# pico_test.net
KiCad netlist of a schematic drawn in EAGLE
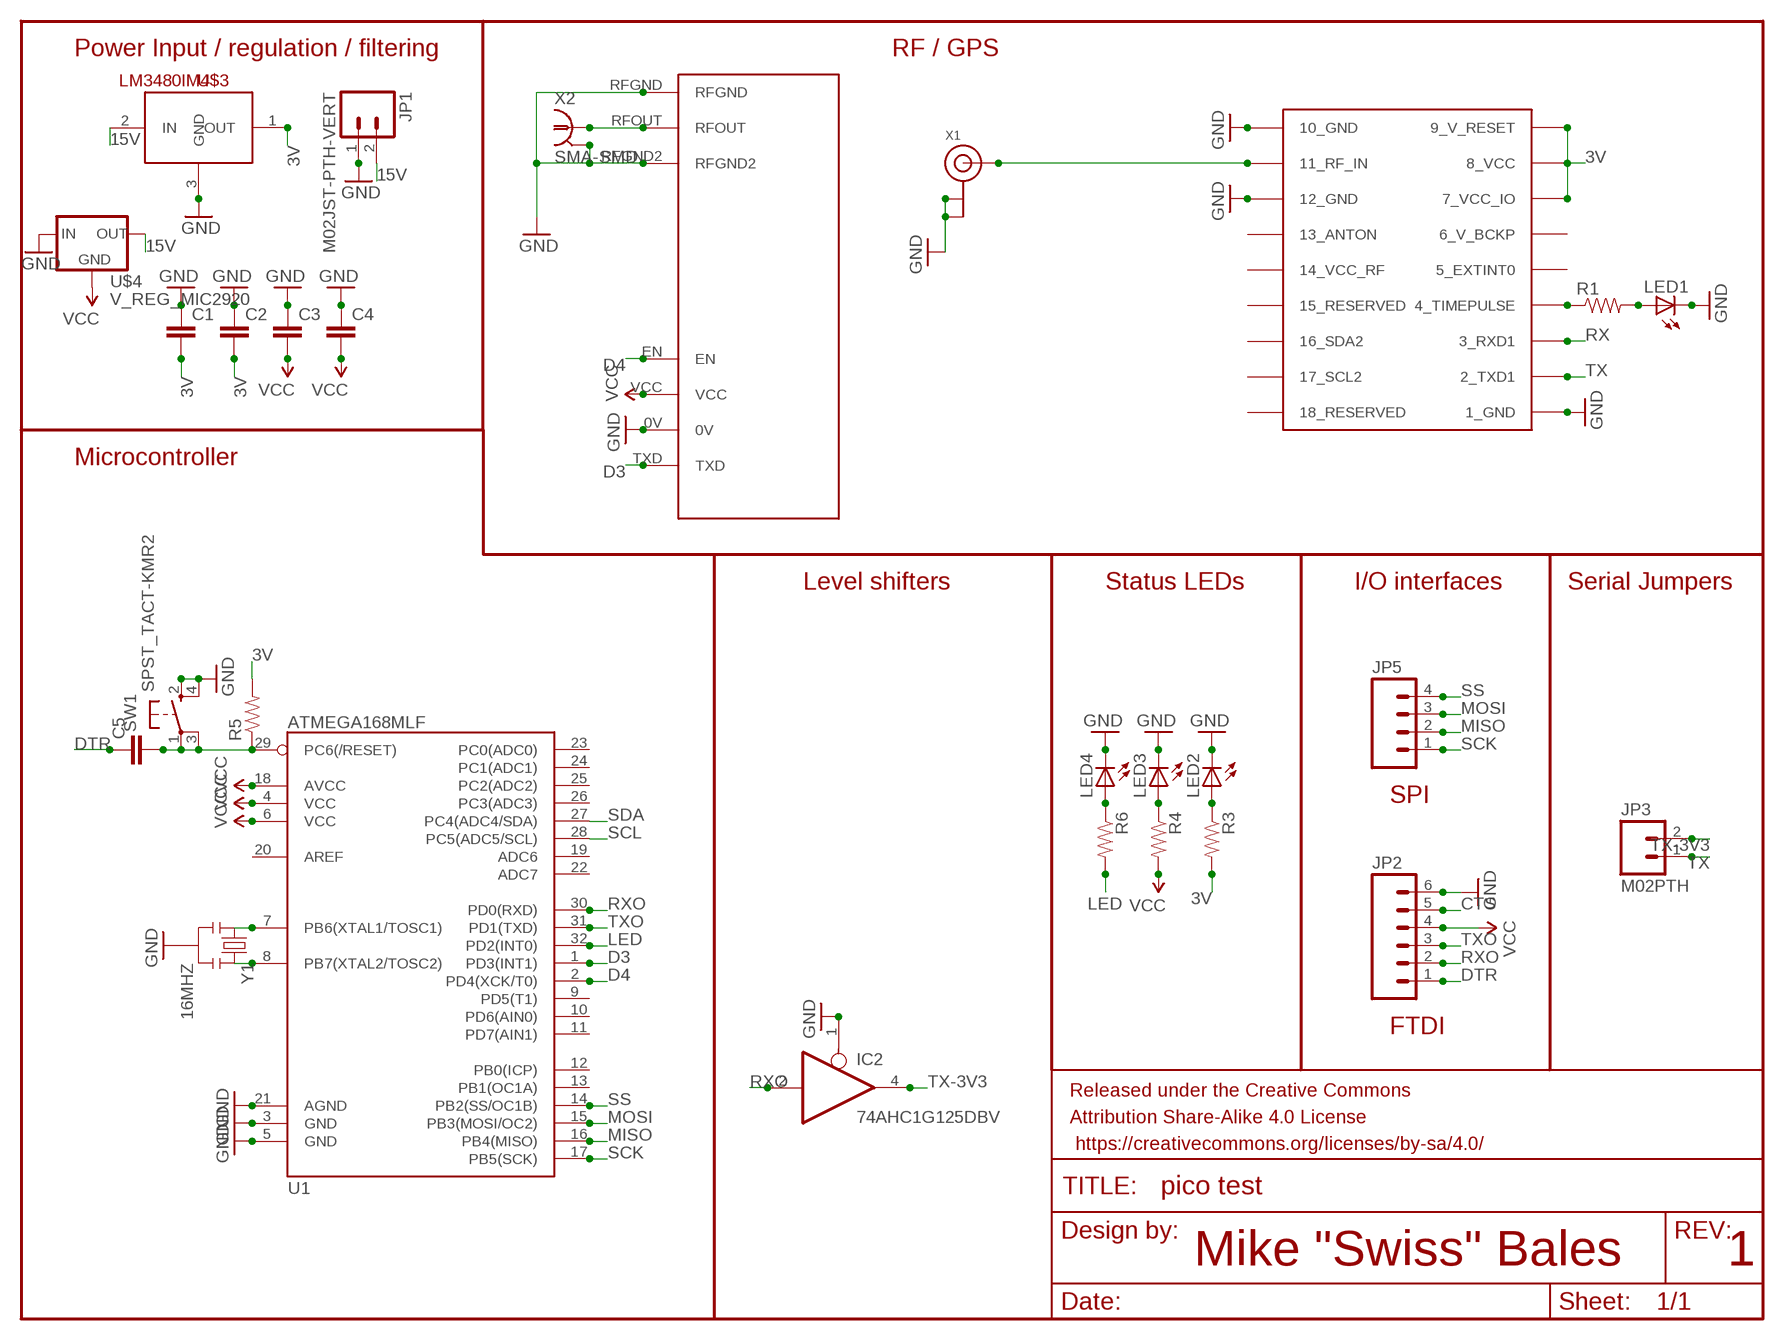
[diagram p0: schematic, sheet 1]

(export (version "E")
  (design (tool "Eeschema 10.0.6"))
  (components
    (comp (ref "C1")
      (value "CAP0805")
      (footprint "eagle-import:0805")
      (libsource (lib "eagle-import") (part "CAP0805"))
    )
    (comp (ref "C2")
      (value "CAP0805")
      (footprint "eagle-import:0805")
      (libsource (lib "eagle-import") (part "CAP0805"))
    )
    (comp (ref "C3")
      (value "CAP0805")
      (footprint "eagle-import:0805")
      (libsource (lib "eagle-import") (part "CAP0805"))
    )
    (comp (ref "C4")
      (value "CAP0805")
      (footprint "eagle-import:0805")
      (libsource (lib "eagle-import") (part "CAP0805"))
    )
    (comp (ref "C5")
      (value "CAP0805")
      (footprint "eagle-import:0805")
      (libsource (lib "eagle-import") (part "CAP0805"))
    )
    (comp (ref "FRAME1")
      (value "FRAME-LETTER")
      (footprint "eagle-import:CREATIVE_COMMONS")
      (libsource (lib "eagle-import") (part "FRAME-LETTER"))
    )
    (comp (ref "IC2")
      (value "74AHC1G125DBV")
      (footprint "eagle-import:SOT23-5")
      (libsource (lib "eagle-import") (part "741G125DBVAHC"))
    )
    (comp (ref "JP1")
      (value "M02JST-PTH-VERT")
      (footprint "eagle-import:JST-2-PTH-VERT")
      (libsource (lib "eagle-import") (part "M02JST-PTH-VERT"))
    )
    (comp (ref "JP2")
      (value "M06NO_SILK_FEMALE_PTH")
      (footprint "eagle-import:1X06_NO_SILK")
      (libsource (lib "eagle-import") (part "M06NO_SILK_FEMALE_PTH"))
    )
    (comp (ref "JP3")
      (value "M02PTH")
      (footprint "eagle-import:1X02")
      (libsource (lib "eagle-import") (part "M02PTH"))
    )
    (comp (ref "JP5")
      (value "M041X04_NO_SILK")
      (footprint "eagle-import:1X04_NO_SILK")
      (libsource (lib "eagle-import") (part "M041X04_NO_SILK"))
    )
    (comp (ref "LED1")
      (value "LEDCHIP-LED0805")
      (footprint "eagle-import:CHIP-LED0805")
      (libsource (lib "eagle-import") (part "LEDCHIP-LED0805"))
    )
    (comp (ref "LED2")
      (value "LEDCHIP-LED0805")
      (footprint "eagle-import:CHIP-LED0805")
      (libsource (lib "eagle-import") (part "LEDCHIP-LED0805"))
    )
    (comp (ref "LED3")
      (value "LEDCHIP-LED0805")
      (footprint "eagle-import:CHIP-LED0805")
      (libsource (lib "eagle-import") (part "LEDCHIP-LED0805"))
    )
    (comp (ref "LED4")
      (value "LEDCHIP-LED0805")
      (footprint "eagle-import:CHIP-LED0805")
      (libsource (lib "eagle-import") (part "LEDCHIP-LED0805"))
    )
    (comp (ref "R1")
      (value "RESISTOR0805-RES")
      (footprint "eagle-import:0805")
      (libsource (lib "eagle-import") (part "RESISTOR0805-RES"))
    )
    (comp (ref "R3")
      (value "RESISTOR0805-RES")
      (footprint "eagle-import:0805")
      (libsource (lib "eagle-import") (part "RESISTOR0805-RES"))
    )
    (comp (ref "R4")
      (value "RESISTOR0805-RES")
      (footprint "eagle-import:0805")
      (libsource (lib "eagle-import") (part "RESISTOR0805-RES"))
    )
    (comp (ref "R5")
      (value "RESISTOR0805-RES")
      (footprint "eagle-import:0805")
      (libsource (lib "eagle-import") (part "RESISTOR0805-RES"))
    )
    (comp (ref "R6")
      (value "RESISTOR0805-RES")
      (footprint "eagle-import:0805")
      (libsource (lib "eagle-import") (part "RESISTOR0805-RES"))
    )
    (comp (ref "SW1")
      (value "SPST_TACT-KMR2")
      (footprint "eagle-import:KMR2")
      (libsource (lib "eagle-import") (part "SPST_TACT-KMR2"))
    )
    (comp (ref "U$1")
      (value "UBLOX_MAX")
      (footprint "eagle-import:UBLOX_MAX")
      (libsource (lib "eagle-import") (part "UBLOX_MAX"))
    )
    (comp (ref "U$2")
      (value "RADIOMETRIX-HX1")
      (footprint "eagle-import:RADIOMETRIX-HX1")
      (libsource (lib "eagle-import") (part "RADIOMETRIX-HX1"))
    )
    (comp (ref "U$3")
      (value "LM3480IM4")
      (footprint "eagle-import:SOT23-3")
      (libsource (lib "eagle-import") (part "LM3480IM4"))
    )
    (comp (ref "U$4")
      (value "V_REG_MIC2920")
      (footprint "eagle-import:SOT223")
      (libsource (lib "eagle-import") (part "V_REG_MIC2920"))
    )
    (comp (ref "U1")
      (value "ATMEGA168MLF")
      (footprint "eagle-import:MLF32")
      (libsource (lib "eagle-import") (part "ATMEGA168MLF"))
    )
    (comp (ref "X1")
      (value "ANTENNA_U.FL")
      (footprint "eagle-import:U.FL")
      (libsource (lib "eagle-import") (part "ANTENNA_U.FL"))
    )
    (comp (ref "X2")
      (value "SMA-SMD")
      (footprint "eagle-import:SMA-SMD")
      (libsource (lib "eagle-import") (part "SMA-SMD"))
    )
    (comp (ref "Y1")
      (value "16MHZ")
      (footprint "eagle-import:RESONATOR-SMD")
      (libsource (lib "eagle-import") (part "RESONATOR16MHZ"))
    )
  )
  (nets
    (net (code "1") (name "/3V") (class "Default")
      (node (ref "C1") (pin "2") (pinfunction "2_2") (pintype "passive"))
      (node (ref "C2") (pin "2") (pinfunction "2_2") (pintype "passive"))
      (node (ref "R3") (pin "2") (pinfunction "2_2") (pintype "passive"))
      (node (ref "R5") (pin "2") (pinfunction "2_2") (pintype "passive"))
      (node (ref "U$1") (pin "7_VCC_IO") (pinfunction "7_VCC_IO_7_VCC_IO") (pintype "power_in"))
      (node (ref "U$1") (pin "8_VCC") (pinfunction "8_VCC_8_VCC") (pintype "power_in"))
      (node (ref "U$1") (pin "9_V_RESET") (pinfunction "9_V_RESET_9_V_RESET") (pintype "power_in"))
      (node (ref "U$3") (pin "1") (pinfunction "OUT_1") (pintype "bidirectional"))
    )
    (net (code "2") (name "/15V") (class "Default")
      (node (ref "JP1") (pin "2") (pinfunction "2_2") (pintype "passive"))
      (node (ref "U$3") (pin "2") (pinfunction "IN_2") (pintype "bidirectional"))
      (node (ref "U$4") (pin "3") (pinfunction "OUT_3") (pintype "output"))
    )
    (net (code "3") (name "/CTS") (class "Default")
      (node (ref "JP2") (pin "5") (pinfunction "5_5") (pintype "passive"))
    )
    (net (code "4") (name "/D3") (class "Default")
      (node (ref "U$2") (pin "TXD") (pinfunction "TXD_TXD") (pintype "bidirectional"))
      (node (ref "U1") (pin "1") (pinfunction "PD3(INT1)_1") (pintype "bidirectional"))
    )
    (net (code "5") (name "/D4") (class "Default")
      (node (ref "U$2") (pin "EN") (pinfunction "EN_EN") (pintype "bidirectional"))
      (node (ref "U1") (pin "2") (pinfunction "PD4(XCK/T0)_2") (pintype "bidirectional"))
    )
    (net (code "6") (name "/DTR") (class "Default")
      (node (ref "C5") (pin "1") (pinfunction "1_1") (pintype "passive"))
      (node (ref "JP2") (pin "1") (pinfunction "1_1") (pintype "passive"))
    )
    (net (code "7") (name "/LED") (class "Default")
      (node (ref "R6") (pin "2") (pinfunction "2_2") (pintype "passive"))
      (node (ref "U1") (pin "32") (pinfunction "PD2(INT0)_32") (pintype "bidirectional"))
    )
    (net (code "8") (name "/MISO") (class "Default")
      (node (ref "JP5") (pin "2") (pinfunction "2_2") (pintype "passive"))
      (node (ref "U1") (pin "16") (pinfunction "PB4(MISO)_16") (pintype "bidirectional"))
    )
    (net (code "9") (name "/MOSI") (class "Default")
      (node (ref "JP5") (pin "3") (pinfunction "3_3") (pintype "passive"))
      (node (ref "U1") (pin "15") (pinfunction "PB3(MOSI/OC2)_15") (pintype "bidirectional"))
    )
    (net (code "10") (name "/RX") (class "Default")
      (node (ref "U$1") (pin "3_RXD1") (pinfunction "3_RXD1_3_RXD1") (pintype "bidirectional"))
    )
    (net (code "11") (name "/RXO") (class "Default")
      (node (ref "IC2") (pin "2") (pinfunction "I_2") (pintype "input"))
      (node (ref "JP2") (pin "2") (pinfunction "2_2") (pintype "passive"))
      (node (ref "U1") (pin "30") (pinfunction "PD0(RXD)_30") (pintype "bidirectional"))
    )
    (net (code "12") (name "/SCK") (class "Default")
      (node (ref "JP5") (pin "1") (pinfunction "1_1") (pintype "passive"))
      (node (ref "U1") (pin "17") (pinfunction "PB5(SCK)_17") (pintype "bidirectional"))
    )
    (net (code "13") (name "/SCL") (class "Default")
      (node (ref "U1") (pin "28") (pinfunction "PC5(ADC5/SCL)_28") (pintype "bidirectional"))
    )
    (net (code "14") (name "/SDA") (class "Default")
      (node (ref "U1") (pin "27") (pinfunction "PC4(ADC4/SDA)_27") (pintype "bidirectional"))
    )
    (net (code "15") (name "/SS") (class "Default")
      (node (ref "JP5") (pin "4") (pinfunction "4_4") (pintype "passive"))
      (node (ref "U1") (pin "14") (pinfunction "PB2(SS/OC1B)_14") (pintype "bidirectional"))
    )
    (net (code "16") (name "/TX") (class "Default")
      (node (ref "JP3") (pin "1") (pinfunction "1_1") (pintype "passive"))
      (node (ref "U$1") (pin "2_TXD1") (pinfunction "2_TXD1_2_TXD1") (pintype "bidirectional"))
    )
    (net (code "17") (name "/TX-3V3") (class "Default")
      (node (ref "IC2") (pin "4") (pinfunction "O_4") (pintype "tri_state"))
      (node (ref "JP3") (pin "2") (pinfunction "2_2") (pintype "passive"))
    )
    (net (code "18") (name "/TXO") (class "Default")
      (node (ref "JP2") (pin "3") (pinfunction "3_3") (pintype "passive"))
      (node (ref "U1") (pin "31") (pinfunction "PD1(TXD)_31") (pintype "bidirectional"))
    )
    (net (code "19") (name "GND") (class "Default")
      (node (ref "C1") (pin "1") (pinfunction "1_1") (pintype "passive"))
      (node (ref "C2") (pin "1") (pinfunction "1_1") (pintype "passive"))
      (node (ref "C3") (pin "1") (pinfunction "1_1") (pintype "passive"))
      (node (ref "C4") (pin "1") (pinfunction "1_1") (pintype "passive"))
      (node (ref "IC2") (pin "1") (pinfunction "OE_1") (pintype "input"))
      (node (ref "JP1") (pin "1") (pinfunction "1_1") (pintype "passive"))
      (node (ref "JP2") (pin "6") (pinfunction "6_6") (pintype "passive"))
      (node (ref "LED1") (pin "C") (pinfunction "C_C") (pintype "passive"))
      (node (ref "LED2") (pin "C") (pinfunction "C_C") (pintype "passive"))
      (node (ref "LED3") (pin "C") (pinfunction "C_C") (pintype "passive"))
      (node (ref "LED4") (pin "C") (pinfunction "C_C") (pintype "passive"))
      (node (ref "SW1") (pin "2") (pinfunction "S_2") (pintype "passive"))
      (node (ref "SW1") (pin "4") (pinfunction "S1_4") (pintype "passive"))
      (node (ref "U$1") (pin "10_GND") (pinfunction "10_GND_10_GND") (pintype "power_in"))
      (node (ref "U$1") (pin "12_GND") (pinfunction "12_GND_12_GND") (pintype "power_in"))
      (node (ref "U$1") (pin "1_GND") (pinfunction "1_GND_1_GND") (pintype "power_in"))
      (node (ref "U$2") (pin "0V") (pinfunction "0V_0V") (pintype "bidirectional"))
      (node (ref "U$2") (pin "RFGND") (pinfunction "RFGND_RFGND") (pintype "bidirectional"))
      (node (ref "U$2") (pin "RFGND2") (pinfunction "RFGND2_RFGND2") (pintype "bidirectional"))
      (node (ref "U$3") (pin "3") (pinfunction "GND_3") (pintype "bidirectional"))
      (node (ref "U$4") (pin "1") (pinfunction "IN_1") (pintype "input"))
      (node (ref "U1") (pin "21") (pinfunction "AGND_21") (pintype "bidirectional"))
      (node (ref "U1") (pin "3") (pinfunction "GND_3") (pintype "bidirectional"))
      (node (ref "U1") (pin "5") (pinfunction "GND_5") (pintype "bidirectional"))
      (node (ref "X1") (pin "1") (pinfunction "GND_1") (pintype "passive"))
      (node (ref "X1") (pin "2") (pinfunction "GND_2") (pintype "passive"))
      (node (ref "X2") (pin "2@1") (pinfunction "2_2@1") (pintype "passive"))
      (node (ref "X2") (pin "2@2") (pinfunction "2_2@2") (pintype "passive"))
      (node (ref "X2") (pin "2@3") (pinfunction "2_2@3") (pintype "passive"))
      (node (ref "X2") (pin "2@4") (pinfunction "2_2@4") (pintype "passive"))
      (node (ref "X2") (pin "2@5") (pinfunction "2_2@5") (pintype "passive"))
      (node (ref "X2") (pin "2@6") (pinfunction "2_2@6") (pintype "passive"))
      (node (ref "Y1") (pin "2") (pinfunction "2_2") (pintype "passive"))
    )
    (net (code "20") (name "Net-(LED1-PadA)") (class "Default")
      (node (ref "LED1") (pin "A") (pinfunction "A_A") (pintype "passive"))
      (node (ref "R1") (pin "2") (pinfunction "2_2") (pintype "passive"))
    )
    (net (code "21") (name "Net-(LED2-PadA)") (class "Default")
      (node (ref "LED2") (pin "A") (pinfunction "A_A") (pintype "passive"))
      (node (ref "R3") (pin "1") (pinfunction "1_1") (pintype "passive"))
    )
    (net (code "22") (name "Net-(LED3-PadA)") (class "Default")
      (node (ref "LED3") (pin "A") (pinfunction "A_A") (pintype "passive"))
      (node (ref "R4") (pin "1") (pinfunction "1_1") (pintype "passive"))
    )
    (net (code "23") (name "Net-(LED4-PadA)") (class "Default")
      (node (ref "LED4") (pin "A") (pinfunction "A_A") (pintype "passive"))
      (node (ref "R6") (pin "1") (pinfunction "1_1") (pintype "passive"))
    )
    (net (code "24") (name "Net-(R1-Pad1)") (class "Default")
      (node (ref "R1") (pin "1") (pinfunction "1_1") (pintype "passive"))
      (node (ref "U$1") (pin "4_TIMEPULSE") (pinfunction "4_TIMEPULSE_4_TIMEPULSE") (pintype "bidirectional"))
    )
    (net (code "25") (name "Net-(SW1-P)") (class "Default")
      (node (ref "C5") (pin "2") (pinfunction "2_2") (pintype "passive"))
      (node (ref "R5") (pin "1") (pinfunction "1_1") (pintype "passive"))
      (node (ref "SW1") (pin "1") (pinfunction "P_1") (pintype "passive"))
      (node (ref "SW1") (pin "3") (pinfunction "P1_3") (pintype "passive"))
      (node (ref "U1") (pin "29") (pinfunction "PC6(/RESET)_29") (pintype "bidirectional"))
    )
    (net (code "26") (name "Net-(U$2-PadRFOUT)") (class "Default")
      (node (ref "U$2") (pin "RFOUT") (pinfunction "RFOUT_RFOUT") (pintype "bidirectional"))
      (node (ref "X2") (pin "1") (pinfunction "1_1") (pintype "passive"))
    )
    (net (code "27") (name "Net-(U1-PB6(XTAL1{slash}TOSC1))") (class "Default")
      (node (ref "U1") (pin "7") (pinfunction "PB6(XTAL1/TOSC1)_7") (pintype "bidirectional"))
      (node (ref "Y1") (pin "1") (pinfunction "1_1") (pintype "passive"))
    )
    (net (code "28") (name "Net-(U1-PB7(XTAL2{slash}TOSC2))") (class "Default")
      (node (ref "U1") (pin "8") (pinfunction "PB7(XTAL2/TOSC2)_8") (pintype "bidirectional"))
      (node (ref "Y1") (pin "3") (pinfunction "3_3") (pintype "passive"))
    )
    (net (code "29") (name "Net-(X1-SIGNAL)") (class "Default")
      (node (ref "U$1") (pin "11_RF_IN") (pinfunction "11_RF_IN_11_RF_IN") (pintype "bidirectional"))
      (node (ref "X1") (pin "3") (pinfunction "SIGNAL_3") (pintype "passive"))
    )
    (net (code "30") (name "VCC") (class "Default")
      (node (ref "C3") (pin "2") (pinfunction "2_2") (pintype "passive"))
      (node (ref "C4") (pin "2") (pinfunction "2_2") (pintype "passive"))
      (node (ref "JP2") (pin "4") (pinfunction "4_4") (pintype "passive"))
      (node (ref "R4") (pin "2") (pinfunction "2_2") (pintype "passive"))
      (node (ref "U$2") (pin "VCC") (pinfunction "VCC_VCC") (pintype "bidirectional"))
      (node (ref "U$4") (pin "2") (pinfunction "GND_2") (pintype "input"))
      (node (ref "U1") (pin "18") (pinfunction "AVCC_18") (pintype "bidirectional"))
      (node (ref "U1") (pin "4") (pinfunction "VCC_4") (pintype "bidirectional"))
      (node (ref "U1") (pin "6") (pinfunction "VCC_6") (pintype "bidirectional"))
    )
    (net (code "31") (name "unconnected-(U$1-Pad5_EXTINT0)") (class "Default")
      (node (ref "U$1") (pin "5_EXTINT0") (pinfunction "5_EXTINT0_5_EXTINT0") (pintype "bidirectional"))
    )
    (net (code "32") (name "unconnected-(U$1-Pad6_V_BCKP)") (class "Default")
      (node (ref "U$1") (pin "6_V_BCKP") (pinfunction "6_V_BCKP_6_V_BCKP") (pintype "bidirectional"))
    )
    (net (code "33") (name "unconnected-(U$1-Pad13_ANTON)") (class "Default")
      (node (ref "U$1") (pin "13_ANTON") (pinfunction "13_ANTON_13_ANTON") (pintype "bidirectional"))
    )
    (net (code "34") (name "unconnected-(U$1-Pad14_VCC_RF)") (class "Default")
      (node (ref "U$1") (pin "14_VCC_RF") (pinfunction "14_VCC_RF_14_VCC_RF") (pintype "bidirectional"))
    )
    (net (code "35") (name "unconnected-(U$1-Pad15_RESERVED)") (class "Default")
      (node (ref "U$1") (pin "15_RESERVED") (pinfunction "15_RESERVED_15_RESERVED") (pintype "bidirectional"))
    )
    (net (code "36") (name "unconnected-(U$1-Pad16_SDA2)") (class "Default")
      (node (ref "U$1") (pin "16_SDA2") (pinfunction "16_SDA2_16_SDA2") (pintype "bidirectional"))
    )
    (net (code "37") (name "unconnected-(U$1-Pad17_SCL2)") (class "Default")
      (node (ref "U$1") (pin "17_SCL2") (pinfunction "17_SCL2_17_SCL2") (pintype "bidirectional"))
    )
    (net (code "38") (name "unconnected-(U$1-Pad18_RESERVED)") (class "Default")
      (node (ref "U$1") (pin "18_RESERVED") (pinfunction "18_RESERVED_18_RESERVED") (pintype "bidirectional"))
    )
    (net (code "39") (name "unconnected-(U1-ADC6-Pad19)") (class "Default")
      (node (ref "U1") (pin "19") (pinfunction "ADC6_19") (pintype "bidirectional"))
    )
    (net (code "40") (name "unconnected-(U1-ADC7-Pad22)") (class "Default")
      (node (ref "U1") (pin "22") (pinfunction "ADC7_22") (pintype "bidirectional"))
    )
    (net (code "41") (name "unconnected-(U1-AREF-Pad20)") (class "Default")
      (node (ref "U1") (pin "20") (pinfunction "AREF_20") (pintype "bidirectional"))
    )
    (net (code "42") (name "unconnected-(U1-PB0(ICP)-Pad12)") (class "Default")
      (node (ref "U1") (pin "12") (pinfunction "PB0(ICP)_12") (pintype "bidirectional"))
    )
    (net (code "43") (name "unconnected-(U1-PB1(OC1A)-Pad13)") (class "Default")
      (node (ref "U1") (pin "13") (pinfunction "PB1(OC1A)_13") (pintype "bidirectional"))
    )
    (net (code "44") (name "unconnected-(U1-PC0(ADC0)-Pad23)") (class "Default")
      (node (ref "U1") (pin "23") (pinfunction "PC0(ADC0)_23") (pintype "bidirectional"))
    )
    (net (code "45") (name "unconnected-(U1-PC1(ADC1)-Pad24)") (class "Default")
      (node (ref "U1") (pin "24") (pinfunction "PC1(ADC1)_24") (pintype "bidirectional"))
    )
    (net (code "46") (name "unconnected-(U1-PC2(ADC2)-Pad25)") (class "Default")
      (node (ref "U1") (pin "25") (pinfunction "PC2(ADC2)_25") (pintype "bidirectional"))
    )
    (net (code "47") (name "unconnected-(U1-PC3(ADC3)-Pad26)") (class "Default")
      (node (ref "U1") (pin "26") (pinfunction "PC3(ADC3)_26") (pintype "bidirectional"))
    )
    (net (code "48") (name "unconnected-(U1-PD5(T1)-Pad9)") (class "Default")
      (node (ref "U1") (pin "9") (pinfunction "PD5(T1)_9") (pintype "bidirectional"))
    )
    (net (code "49") (name "unconnected-(U1-PD6(AIN0)-Pad10)") (class "Default")
      (node (ref "U1") (pin "10") (pinfunction "PD6(AIN0)_10") (pintype "bidirectional"))
    )
    (net (code "50") (name "unconnected-(U1-PD7(AIN1)-Pad11)") (class "Default")
      (node (ref "U1") (pin "11") (pinfunction "PD7(AIN1)_11") (pintype "bidirectional"))
    )
  )
)
